# cytron_st.net
KiCad netlist of a schematic drawn in EAGLE
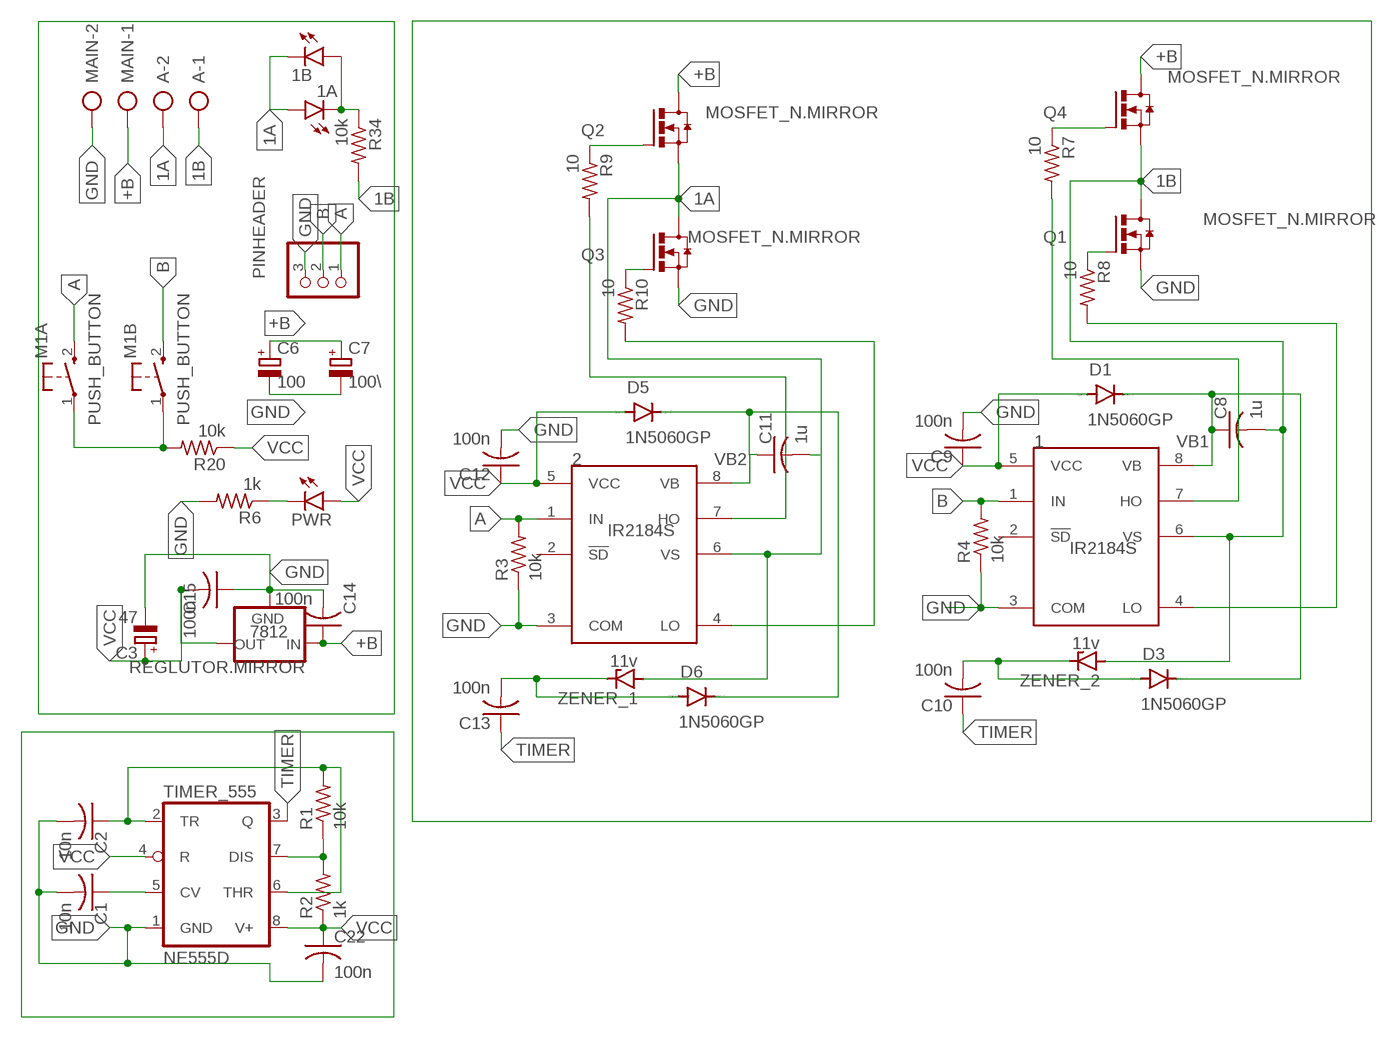
[diagram p0: schematic, sheet 1]

(export (version "E")
  (design (tool "Eeschema 10.0.6"))
  (components
    (comp (ref "1")
      (value "IR2184S")
      (footprint "eagle-import:SO08")
      (libsource (lib "eagle-import") (part "IR2184S"))
    )
    (comp (ref "1A")
      (value "LED3MM")
      (footprint "eagle-import:LED3MM")
      (libsource (lib "eagle-import") (part "LED3MM"))
    )
    (comp (ref "1B")
      (value "LED3MM")
      (footprint "eagle-import:LED3MM")
      (libsource (lib "eagle-import") (part "LED3MM"))
    )
    (comp (ref "2")
      (value "IR2184S")
      (footprint "eagle-import:SO08")
      (libsource (lib "eagle-import") (part "IR2184S"))
    )
    (comp (ref "7812")
      (value "REGLUTOR.MIRROR")
      (footprint "eagle-import:78XXL.MIRROR")
      (libsource (lib "eagle-import") (part "REGLUTOR.MIRROR"))
    )
    (comp (ref "A")
      (value "AK300/22")
      (footprint "eagle-import:XTALRR488W60L1090T465H350B")
      (libsource (lib "eagle-import") (part "AK300/22"))
    )
    (comp (ref "C1")
      (value "10n")
      (footprint "eagle-import:C025-025X050")
      (libsource (lib "eagle-import") (part "C-US025-025X050"))
    )
    (comp (ref "C2")
      (value "10n")
      (footprint "eagle-import:C025-025X050")
      (libsource (lib "eagle-import") (part "C-US025-025X050"))
    )
    (comp (ref "C3")
      (value "47")
      (footprint "eagle-import:E5-10,5")
      (libsource (lib "eagle-import") (part "CPOL-EUE5-10.5"))
    )
    (comp (ref "C6")
      (value "100")
      (footprint "eagle-import:E5-10,5")
      (libsource (lib "eagle-import") (part "CPOL-EUE5-10.5"))
    )
    (comp (ref "C7")
      (value "100\\")
      (footprint "eagle-import:E5-10,5")
      (libsource (lib "eagle-import") (part "CPOL-EUE5-10.5"))
    )
    (comp (ref "C8")
      (value "1u")
      (footprint "eagle-import:C025-025X050")
      (libsource (lib "eagle-import") (part "rcl_334_C-US025-025X050"))
    )
    (comp (ref "C9")
      (value "100n")
      (footprint "eagle-import:C025-025X050")
      (libsource (lib "eagle-import") (part "C-US025-025X050"))
    )
    (comp (ref "C10")
      (value "100n")
      (footprint "eagle-import:C025-025X050")
      (libsource (lib "eagle-import") (part "C-US025-025X050"))
    )
    (comp (ref "C11")
      (value "1u")
      (footprint "eagle-import:C025-025X050")
      (libsource (lib "eagle-import") (part "rcl_334_C-US025-025X050"))
    )
    (comp (ref "C12")
      (value "100n")
      (footprint "eagle-import:C025-025X050")
      (libsource (lib "eagle-import") (part "C-US025-025X050"))
    )
    (comp (ref "C13")
      (value "100n")
      (footprint "eagle-import:C025-025X050")
      (libsource (lib "eagle-import") (part "C-US025-025X050"))
    )
    (comp (ref "C14")
      (value "100n")
      (footprint "eagle-import:C025-025X050")
      (libsource (lib "eagle-import") (part "C-US025-025X050"))
    )
    (comp (ref "C15")
      (value "100n")
      (footprint "eagle-import:C025-025X050")
      (libsource (lib "eagle-import") (part "C-US025-025X050"))
    )
    (comp (ref "C22")
      (value "100n")
      (footprint "eagle-import:C025-025X050")
      (libsource (lib "eagle-import") (part "C-US025-025X050"))
    )
    (comp (ref "D1")
      (value "1N5060GP")
      (footprint "eagle-import:DO15-12")
      (libsource (lib "eagle-import") (part "1N5060GP"))
    )
    (comp (ref "D3")
      (value "1N5060GP")
      (footprint "eagle-import:DO15-12")
      (libsource (lib "eagle-import") (part "1N5060GP"))
    )
    (comp (ref "D5")
      (value "1N5060GP")
      (footprint "eagle-import:DO15-12")
      (libsource (lib "eagle-import") (part "1N5060GP"))
    )
    (comp (ref "D6")
      (value "1N5060GP")
      (footprint "eagle-import:DO15-12")
      (libsource (lib "eagle-import") (part "1N5060GP"))
    )
    (comp (ref "M1A")
      (value "PUSH_BUTTON")
      (footprint "eagle-import:B3F-10XX")
      (libsource (lib "eagle-import") (part "PUSH_BUTTON"))
    )
    (comp (ref "M1B")
      (value "PUSH_BUTTON")
      (footprint "eagle-import:B3F-10XX")
      (libsource (lib "eagle-import") (part "PUSH_BUTTON"))
    )
    (comp (ref "MAIN")
      (value "AK300/22")
      (footprint "eagle-import:XTALRR488W60L1090T465H350B")
      (libsource (lib "eagle-import") (part "AK300/22"))
    )
    (comp (ref "PINHEADER")
      (value "PINHD-1X3")
      (footprint "eagle-import:1X03")
      (libsource (lib "eagle-import") (part "PINHD-1X3"))
    )
    (comp (ref "PWR")
      (value "LED5MM")
      (footprint "eagle-import:LED5MM")
      (libsource (lib "eagle-import") (part "LED5MM"))
    )
    (comp (ref "Q1")
      (value "MOSFET_N.MIRROR")
      (footprint "eagle-import:TO220.MIRROR")
      (libsource (lib "eagle-import") (part "MOSFET_N.MIRROR"))
    )
    (comp (ref "Q2")
      (value "MOSFET_N.MIRROR")
      (footprint "eagle-import:TO220.MIRROR")
      (libsource (lib "eagle-import") (part "MOSFET_N.MIRROR"))
    )
    (comp (ref "Q3")
      (value "MOSFET_N.MIRROR")
      (footprint "eagle-import:TO220.MIRROR")
      (libsource (lib "eagle-import") (part "MOSFET_N.MIRROR"))
    )
    (comp (ref "Q4")
      (value "MOSFET_N.MIRROR")
      (footprint "eagle-import:TO220.MIRROR")
      (libsource (lib "eagle-import") (part "MOSFET_N.MIRROR"))
    )
    (comp (ref "R1")
      (value "10k")
      (footprint "eagle-import:0207_2V")
      (libsource (lib "eagle-import") (part "R-US_0207/2V"))
    )
    (comp (ref "R2")
      (value "1k")
      (footprint "eagle-import:0207_2V")
      (libsource (lib "eagle-import") (part "R-US_0207/2V"))
    )
    (comp (ref "R3")
      (value "10k")
      (footprint "eagle-import:0207_2V")
      (libsource (lib "eagle-import") (part "R-US_0207/2V"))
    )
    (comp (ref "R4")
      (value "10k")
      (footprint "eagle-import:0207_2V")
      (libsource (lib "eagle-import") (part "R-US_0207/2V"))
    )
    (comp (ref "R6")
      (value "1k")
      (footprint "eagle-import:0207_5V")
      (libsource (lib "eagle-import") (part "R-US_0207/5V"))
    )
    (comp (ref "R7")
      (value "10")
      (footprint "eagle-import:0207_5V")
      (libsource (lib "eagle-import") (part "R-US_0207/5V"))
    )
    (comp (ref "R8")
      (value "10")
      (footprint "eagle-import:0207_5V")
      (libsource (lib "eagle-import") (part "R-US_0207/5V"))
    )
    (comp (ref "R9")
      (value "10")
      (footprint "eagle-import:0207_5V")
      (libsource (lib "eagle-import") (part "R-US_0207/5V"))
    )
    (comp (ref "R10")
      (value "10")
      (footprint "eagle-import:0207_5V")
      (libsource (lib "eagle-import") (part "R-US_0207/5V"))
    )
    (comp (ref "R20")
      (value "10k")
      (footprint "eagle-import:0207_5V")
      (libsource (lib "eagle-import") (part "R-US_0207/5V"))
    )
    (comp (ref "R34")
      (value "10k")
      (footprint "eagle-import:0207_5V")
      (libsource (lib "eagle-import") (part "R-US_0207/5V"))
    )
    (comp (ref "TIMER_555")
      (value "NE555D")
      (footprint "eagle-import:SO08")
      (libsource (lib "eagle-import") (part "555DNE"))
    )
    (comp (ref "ZENER_1")
      (value "11v")
      (footprint "eagle-import:SOD81")
      (libsource (lib "eagle-import") (part "BZD23"))
    )
    (comp (ref "ZENER_2")
      (value "11v")
      (footprint "eagle-import:SOD81")
      (libsource (lib "eagle-import") (part "BZD23"))
    )
  )
  (nets
    (net (code "1") (name "+B") (class "Default")
      (node (ref "7812") (pin "IN") (pinfunction "IN_IN") (pintype "input"))
      (node (ref "C14") (pin "1") (pinfunction "1_1") (pintype "passive"))
      (node (ref "C6") (pin "+") (pinfunction "+_+") (pintype "passive"))
      (node (ref "C7") (pin "+") (pinfunction "+_+") (pintype "passive"))
      (node (ref "MAIN") (pin "1") (pinfunction "KL_1") (pintype "passive"))
      (node (ref "Q2") (pin "D") (pinfunction "D_D") (pintype "passive"))
      (node (ref "Q4") (pin "D") (pinfunction "D_D") (pintype "passive"))
    )
    (net (code "2") (name "/VB1") (class "Default")
      (node (ref "1") (pin "8") (pinfunction "VB_8") (pintype "power_in"))
      (node (ref "C8") (pin "1") (pinfunction "1_1") (pintype "passive"))
      (node (ref "D1") (pin "C") (pinfunction "C_C") (pintype "passive"))
      (node (ref "D3") (pin "C") (pinfunction "C_C") (pintype "passive"))
    )
    (net (code "3") (name "/VB2") (class "Default")
      (node (ref "2") (pin "8") (pinfunction "VB_8") (pintype "power_in"))
      (node (ref "C11") (pin "1") (pinfunction "1_1") (pintype "passive"))
      (node (ref "D5") (pin "C") (pinfunction "C_C") (pintype "passive"))
      (node (ref "D6") (pin "C") (pinfunction "C_C") (pintype "passive"))
    )
    (net (code "4") (name "1A") (class "Default")
      (node (ref "1A") (pin "A") (pinfunction "A_A") (pintype "passive"))
      (node (ref "1B") (pin "K") (pinfunction "C_K") (pintype "passive"))
      (node (ref "2") (pin "6") (pinfunction "VS_6") (pintype "power_in"))
      (node (ref "A") (pin "2") (pinfunction "KL_2") (pintype "passive"))
      (node (ref "C11") (pin "2") (pinfunction "2_2") (pintype "passive"))
      (node (ref "Q2") (pin "S") (pinfunction "S_S") (pintype "passive"))
      (node (ref "Q3") (pin "D") (pinfunction "D_D") (pintype "passive"))
      (node (ref "ZENER_1") (pin "A") (pinfunction "A_A") (pintype "passive"))
    )
    (net (code "5") (name "1B") (class "Default")
      (node (ref "1") (pin "6") (pinfunction "VS_6") (pintype "power_in"))
      (node (ref "A") (pin "1") (pinfunction "KL_1") (pintype "passive"))
      (node (ref "C8") (pin "2") (pinfunction "2_2") (pintype "passive"))
      (node (ref "Q1") (pin "D") (pinfunction "D_D") (pintype "passive"))
      (node (ref "Q4") (pin "S") (pinfunction "S_S") (pintype "passive"))
      (node (ref "R34") (pin "2") (pinfunction "2_2") (pintype "passive"))
      (node (ref "ZENER_2") (pin "A") (pinfunction "A_A") (pintype "passive"))
    )
    (net (code "6") (name "A") (class "Default")
      (node (ref "2") (pin "1") (pinfunction "IN_1") (pintype "input"))
      (node (ref "M1A") (pin "2") (pinfunction "S_2") (pintype "passive"))
      (node (ref "PINHEADER") (pin "1") (pinfunction "1_1") (pintype "passive"))
      (node (ref "R3") (pin "2") (pinfunction "2_2") (pintype "passive"))
    )
    (net (code "7") (name "B") (class "Default")
      (node (ref "1") (pin "1") (pinfunction "IN_1") (pintype "input"))
      (node (ref "M1B") (pin "2") (pinfunction "S_2") (pintype "passive"))
      (node (ref "PINHEADER") (pin "2") (pinfunction "2_2") (pintype "passive"))
      (node (ref "R4") (pin "2") (pinfunction "2_2") (pintype "passive"))
    )
    (net (code "8") (name "GND") (class "Default")
      (node (ref "1") (pin "3") (pinfunction "COM_3") (pintype "power_in"))
      (node (ref "2") (pin "3") (pinfunction "COM_3") (pintype "power_in"))
      (node (ref "7812") (pin "GND") (pinfunction "GND_GND") (pintype "input"))
      (node (ref "C1") (pin "2") (pinfunction "2_2") (pintype "passive"))
      (node (ref "C12") (pin "2") (pinfunction "2_2") (pintype "passive"))
      (node (ref "C14") (pin "2") (pinfunction "2_2") (pintype "passive"))
      (node (ref "C15") (pin "1") (pinfunction "1_1") (pintype "passive"))
      (node (ref "C2") (pin "2") (pinfunction "2_2") (pintype "passive"))
      (node (ref "C22") (pin "2") (pinfunction "2_2") (pintype "passive"))
      (node (ref "C3") (pin "-") (pinfunction "-_-") (pintype "passive"))
      (node (ref "C6") (pin "-") (pinfunction "-_-") (pintype "passive"))
      (node (ref "C7") (pin "-") (pinfunction "-_-") (pintype "passive"))
      (node (ref "C9") (pin "2") (pinfunction "2_2") (pintype "passive"))
      (node (ref "MAIN") (pin "2") (pinfunction "KL_2") (pintype "passive"))
      (node (ref "PINHEADER") (pin "3") (pinfunction "3_3") (pintype "passive"))
      (node (ref "Q1") (pin "S") (pinfunction "S_S") (pintype "passive"))
      (node (ref "Q3") (pin "S") (pinfunction "S_S") (pintype "passive"))
      (node (ref "R3") (pin "1") (pinfunction "1_1") (pintype "passive"))
      (node (ref "R4") (pin "1") (pinfunction "1_1") (pintype "passive"))
      (node (ref "R6") (pin "2") (pinfunction "2_2") (pintype "passive"))
      (node (ref "TIMER_555") (pin "1") (pinfunction "GND_1") (pintype "power_in"))
    )
    (net (code "9") (name "Net-(1-HO)") (class "Default")
      (node (ref "1") (pin "7") (pinfunction "HO_7") (pintype "output"))
      (node (ref "R7") (pin "2") (pinfunction "2_2") (pintype "passive"))
    )
    (net (code "10") (name "Net-(1-LO)") (class "Default")
      (node (ref "1") (pin "4") (pinfunction "LO_4") (pintype "output"))
      (node (ref "R8") (pin "2") (pinfunction "2_2") (pintype "passive"))
    )
    (net (code "11") (name "Net-(1A-C)") (class "Default")
      (node (ref "1A") (pin "K") (pinfunction "C_K") (pintype "passive"))
      (node (ref "1B") (pin "A") (pinfunction "A_A") (pintype "passive"))
      (node (ref "R34") (pin "1") (pinfunction "1_1") (pintype "passive"))
    )
    (net (code "12") (name "Net-(2-HO)") (class "Default")
      (node (ref "2") (pin "7") (pinfunction "HO_7") (pintype "output"))
      (node (ref "R9") (pin "2") (pinfunction "2_2") (pintype "passive"))
    )
    (net (code "13") (name "Net-(2-LO)") (class "Default")
      (node (ref "2") (pin "4") (pinfunction "LO_4") (pintype "output"))
      (node (ref "R10") (pin "2") (pinfunction "2_2") (pintype "passive"))
    )
    (net (code "14") (name "Net-(C10-Pad2)") (class "Default")
      (node (ref "C10") (pin "2") (pinfunction "2_2") (pintype "passive"))
      (node (ref "D3") (pin "A") (pinfunction "A_A") (pintype "passive"))
      (node (ref "ZENER_2") (pin "C") (pinfunction "C_C") (pintype "passive"))
    )
    (net (code "15") (name "Net-(C13-Pad2)") (class "Default")
      (node (ref "C13") (pin "2") (pinfunction "2_2") (pintype "passive"))
      (node (ref "D6") (pin "A") (pinfunction "A_A") (pintype "passive"))
      (node (ref "ZENER_1") (pin "C") (pinfunction "C_C") (pintype "passive"))
    )
    (net (code "16") (name "Net-(M1A-P)") (class "Default")
      (node (ref "M1A") (pin "1") (pinfunction "P_1") (pintype "passive"))
      (node (ref "M1B") (pin "1") (pinfunction "P_1") (pintype "passive"))
      (node (ref "R20") (pin "2") (pinfunction "2_2") (pintype "passive"))
    )
    (net (code "17") (name "Net-(PWR-C)") (class "Default")
      (node (ref "PWR") (pin "K") (pinfunction "C_K") (pintype "passive"))
      (node (ref "R6") (pin "1") (pinfunction "1_1") (pintype "passive"))
    )
    (net (code "18") (name "Net-(Q1-PadG)") (class "Default")
      (node (ref "Q1") (pin "G") (pinfunction "G_G") (pintype "passive"))
      (node (ref "R8") (pin "1") (pinfunction "1_1") (pintype "passive"))
    )
    (net (code "19") (name "Net-(Q2-PadG)") (class "Default")
      (node (ref "Q2") (pin "G") (pinfunction "G_G") (pintype "passive"))
      (node (ref "R9") (pin "1") (pinfunction "1_1") (pintype "passive"))
    )
    (net (code "20") (name "Net-(Q3-PadG)") (class "Default")
      (node (ref "Q3") (pin "G") (pinfunction "G_G") (pintype "passive"))
      (node (ref "R10") (pin "1") (pinfunction "1_1") (pintype "passive"))
    )
    (net (code "21") (name "Net-(Q4-PadG)") (class "Default")
      (node (ref "Q4") (pin "G") (pinfunction "G_G") (pintype "passive"))
      (node (ref "R7") (pin "1") (pinfunction "1_1") (pintype "passive"))
    )
    (net (code "22") (name "Net-(TIMER_555-CV)") (class "Default")
      (node (ref "C1") (pin "1") (pinfunction "1_1") (pintype "passive"))
      (node (ref "TIMER_555") (pin "5") (pinfunction "CV_5") (pintype "input"))
    )
    (net (code "23") (name "Net-(TIMER_555-DIS)") (class "Default")
      (node (ref "R1") (pin "1") (pinfunction "1_1") (pintype "passive"))
      (node (ref "R2") (pin "2") (pinfunction "2_2") (pintype "passive"))
      (node (ref "TIMER_555") (pin "7") (pinfunction "DIS_7") (pintype "input"))
    )
    (net (code "24") (name "Net-(TIMER_555-THR)") (class "Default")
      (node (ref "C2") (pin "1") (pinfunction "1_1") (pintype "passive"))
      (node (ref "R1") (pin "2") (pinfunction "2_2") (pintype "passive"))
      (node (ref "TIMER_555") (pin "2") (pinfunction "TR_2") (pintype "input"))
      (node (ref "TIMER_555") (pin "6") (pinfunction "THR_6") (pintype "input"))
    )
    (net (code "25") (name "TIMER") (class "Default")
      (node (ref "C10") (pin "1") (pinfunction "1_1") (pintype "passive"))
      (node (ref "C13") (pin "1") (pinfunction "1_1") (pintype "passive"))
      (node (ref "TIMER_555") (pin "3") (pinfunction "Q_3") (pintype "output"))
    )
    (net (code "26") (name "VCC") (class "Default")
      (node (ref "1") (pin "5") (pinfunction "VCC_5") (pintype "power_in"))
      (node (ref "2") (pin "5") (pinfunction "VCC_5") (pintype "power_in"))
      (node (ref "7812") (pin "OUT") (pinfunction "OUT_OUT") (pintype "passive"))
      (node (ref "C12") (pin "1") (pinfunction "1_1") (pintype "passive"))
      (node (ref "C15") (pin "2") (pinfunction "2_2") (pintype "passive"))
      (node (ref "C22") (pin "1") (pinfunction "1_1") (pintype "passive"))
      (node (ref "C3") (pin "+") (pinfunction "+_+") (pintype "passive"))
      (node (ref "C9") (pin "1") (pinfunction "1_1") (pintype "passive"))
      (node (ref "D1") (pin "A") (pinfunction "A_A") (pintype "passive"))
      (node (ref "D5") (pin "A") (pinfunction "A_A") (pintype "passive"))
      (node (ref "PWR") (pin "A") (pinfunction "A_A") (pintype "passive"))
      (node (ref "R2") (pin "1") (pinfunction "1_1") (pintype "passive"))
      (node (ref "R20") (pin "1") (pinfunction "1_1") (pintype "passive"))
      (node (ref "TIMER_555") (pin "4") (pinfunction "R_4") (pintype "input"))
      (node (ref "TIMER_555") (pin "8") (pinfunction "V+_8") (pintype "power_in"))
    )
    (net (code "27") (name "unconnected-(1-~{SD}-Pad2)") (class "Default")
      (node (ref "1") (pin "2") (pinfunction "~{SD}_2") (pintype "input"))
    )
    (net (code "28") (name "unconnected-(2-~{SD}-Pad2)") (class "Default")
      (node (ref "2") (pin "2") (pinfunction "~{SD}_2") (pintype "input"))
    )
  )
)
